# PSU.net
KiCad netlist of a schematic drawn in Altium Designer
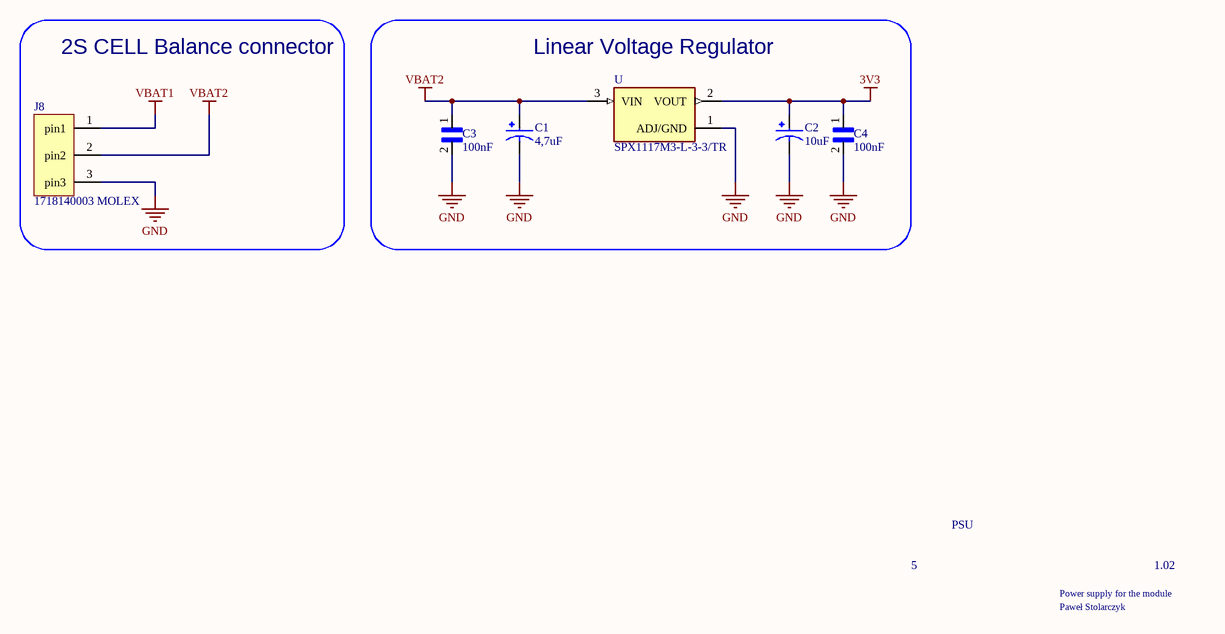
[diagram p0: PSU.SchDoc]

(export (version "E")
  (design (tool "Eeschema 10.0.6"))
  (components
    (comp (ref "C1")
      (value "4,7uF")
      (footprint "CAP_EEE1CA100SR")
      (description "10ÂµF 16V Aluminum Electrolytic Capacitors Radial, Can - SMD 2000 Hrs @ 85Â°C")
      (fields (field (name "MF") "Panasonic") (field (name "DIGI-KEY_PART_NUMBER") "PCE3878CT-ND"))
      (libsource (lib "EEE1CA100SR") (part "EEE1CA100SR"))
    )
    (comp (ref "C2")
      (value "10uF")
      (footprint "CAP_EEE1CA100SR")
      (description "10ÂµF 16V Aluminum Electrolytic Capacitors Radial, Can - SMD 2000 Hrs @ 85Â°C")
      (fields (field (name "MF") "Panasonic") (field (name "DIGI-KEY_PART_NUMBER") "PCE3878CT-ND"))
      (libsource (lib "EEE1CA100SR") (part "EEE1CA100SR"))
    )
    (comp (ref "C3")
      (value "100nF")
      (footprint "CAPC1608X90N")
      (description "0.1ÂµF Â±5% 16V Ceramic Capacitor X7R 0603 (1608 Metric)")
      (fields (field (name "MP") "C0603C104J4RAC") (field (name "MF") "KEMET"))
      (libsource (lib "C0603C104J4RAC") (part "C0603C104J4RAC"))
    )
    (comp (ref "C4")
      (value "100nF")
      (footprint "CAPC1608X90N")
      (description "0.1ÂµF Â±5% 16V Ceramic Capacitor X7R 0603 (1608 Metric)")
      (fields (field (name "MP") "C0603C104J4RAC") (field (name "MF") "KEMET"))
      (libsource (lib "C0603C104J4RAC") (part "C0603C104J4RAC"))
    )
    (comp (ref "J8")
      (value "1718140003 MOLEX")
      (footprint "3pinangled")
      (libsource (lib "zginane3pinowe") (part "3pinangled"))
    )
    (comp (ref "U")
      (value "SPX1117M3-L-3-3/TR")
      (footprint "SOT230P700X180-3N")
      (description "Linear Voltage Regulator IC Positive Fixed 1 Output 800mA SOT-223")
      (fields (field (name "MF") "MaxLinear, Inc."))
      (libsource (lib "SPX1117M3-L-3-3_TR") (part "SPX1117M3-L-3-3/TR"))
    )
  )
  (nets
    (net (code "1") (name "3V3") (class "Default")
      (node (ref "C2") (pin "1") (pinfunction "1_1") (pintype "passive"))
      (node (ref "C4") (pin "1") (pinfunction "1_1") (pintype "passive"))
      (node (ref "U") (pin "2") (pinfunction "VOUT_2") (pintype "output"))
    )
    (net (code "2") (name "GND") (class "Default")
      (node (ref "C1") (pin "2") (pinfunction "2_2") (pintype "passive"))
      (node (ref "C2") (pin "2") (pinfunction "2_2") (pintype "passive"))
      (node (ref "C3") (pin "2") (pinfunction "2_2") (pintype "passive"))
      (node (ref "C4") (pin "2") (pinfunction "2_2") (pintype "passive"))
      (node (ref "J8") (pin "3") (pinfunction "pin3_3") (pintype "passive"))
      (node (ref "U") (pin "1") (pinfunction "ADJ/GND_1") (pintype "power_in"))
    )
    (net (code "3") (name "VBAT1") (class "Default")
      (node (ref "J8") (pin "1") (pinfunction "pin1_1") (pintype "passive"))
    )
    (net (code "4") (name "VBAT2") (class "Default")
      (node (ref "C1") (pin "1") (pinfunction "1_1") (pintype "passive"))
      (node (ref "C3") (pin "1") (pinfunction "1_1") (pintype "passive"))
      (node (ref "J8") (pin "2") (pinfunction "pin2_2") (pintype "passive"))
      (node (ref "U") (pin "3") (pinfunction "VIN_3") (pintype "input"))
    )
  )
)
